# CF_Grove_Cape_v0_1.net
KiCad netlist of a schematic drawn in EAGLE
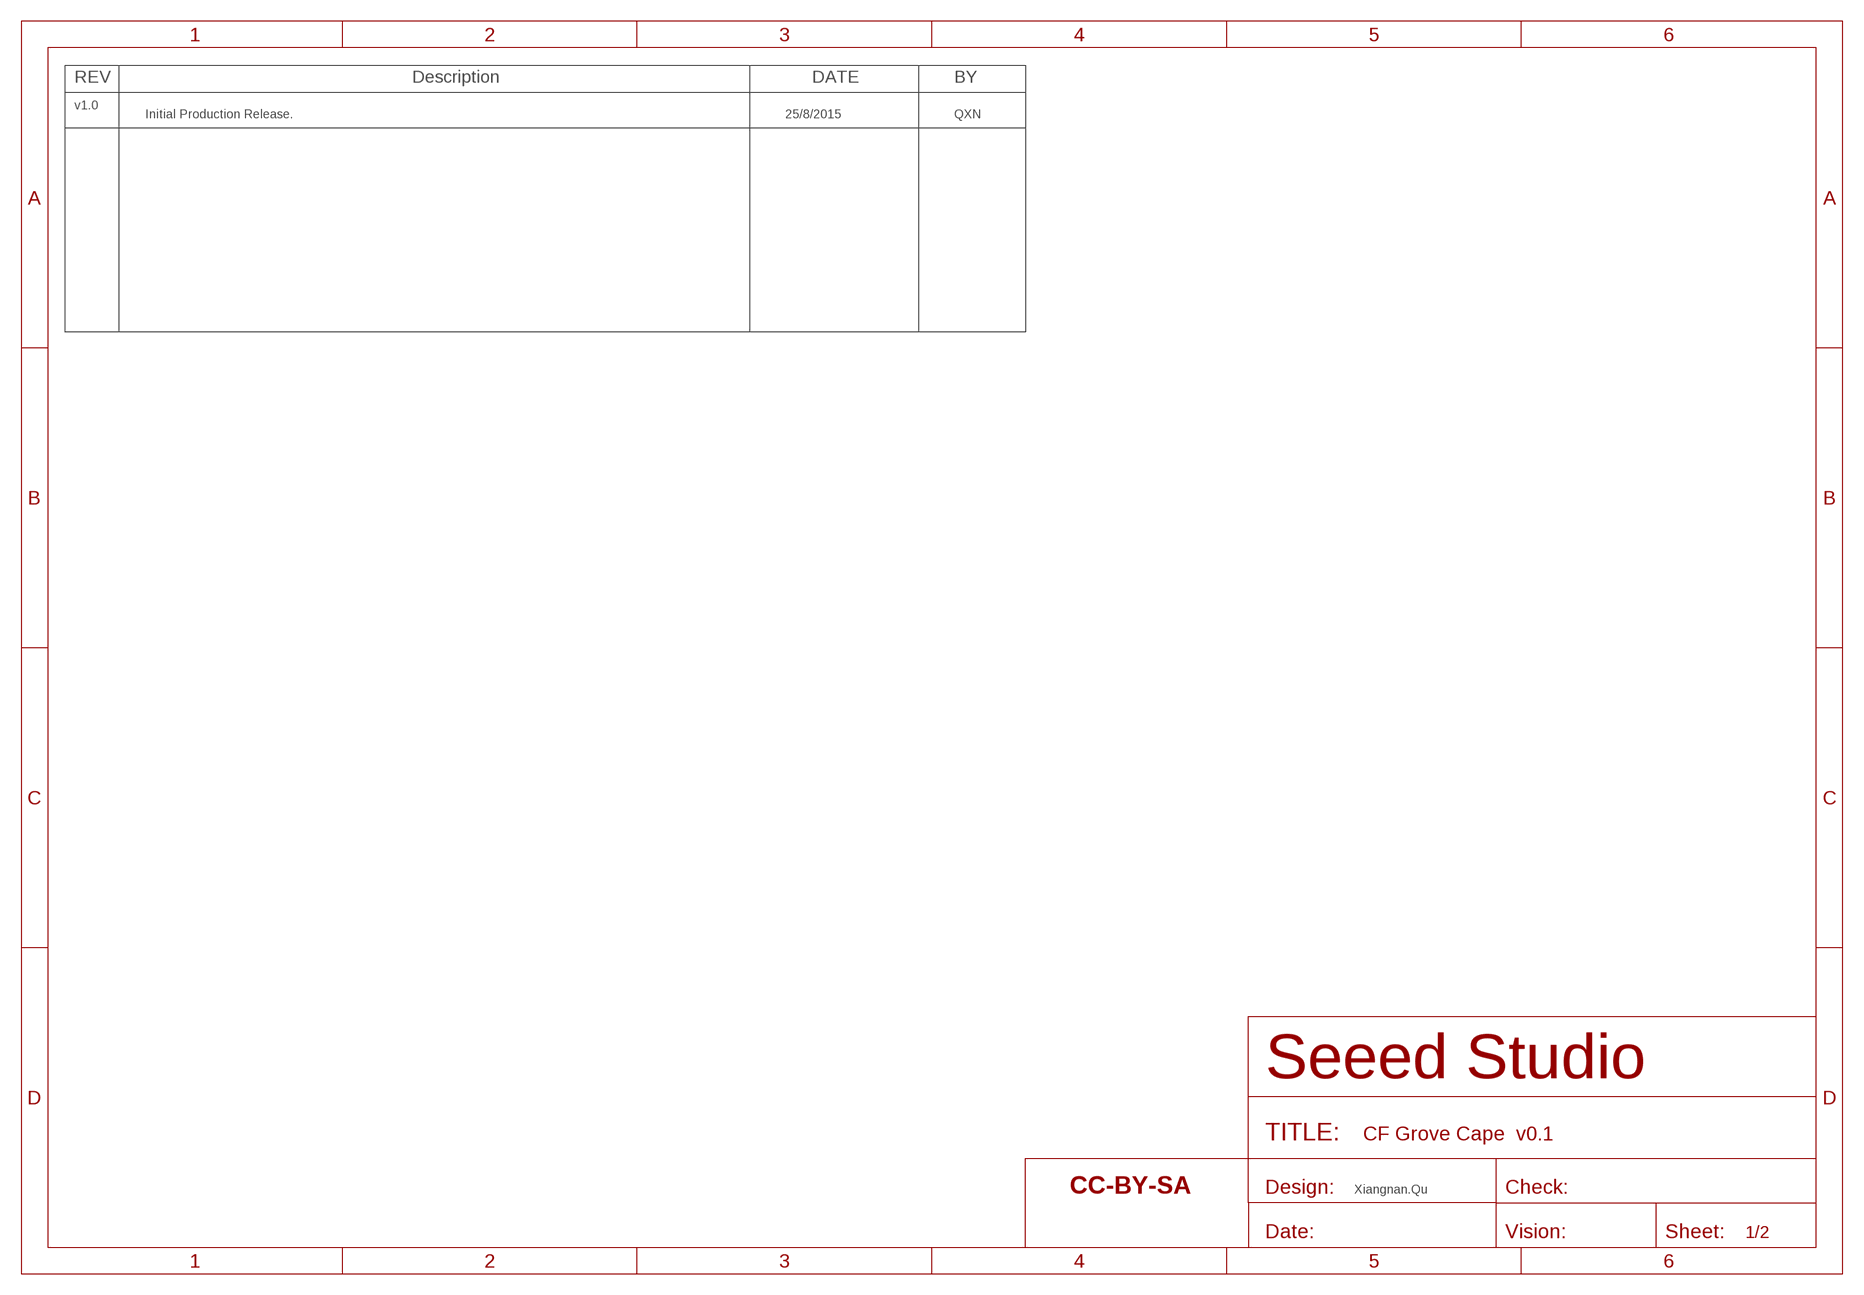
[diagram p0: schematic, sheet 1]
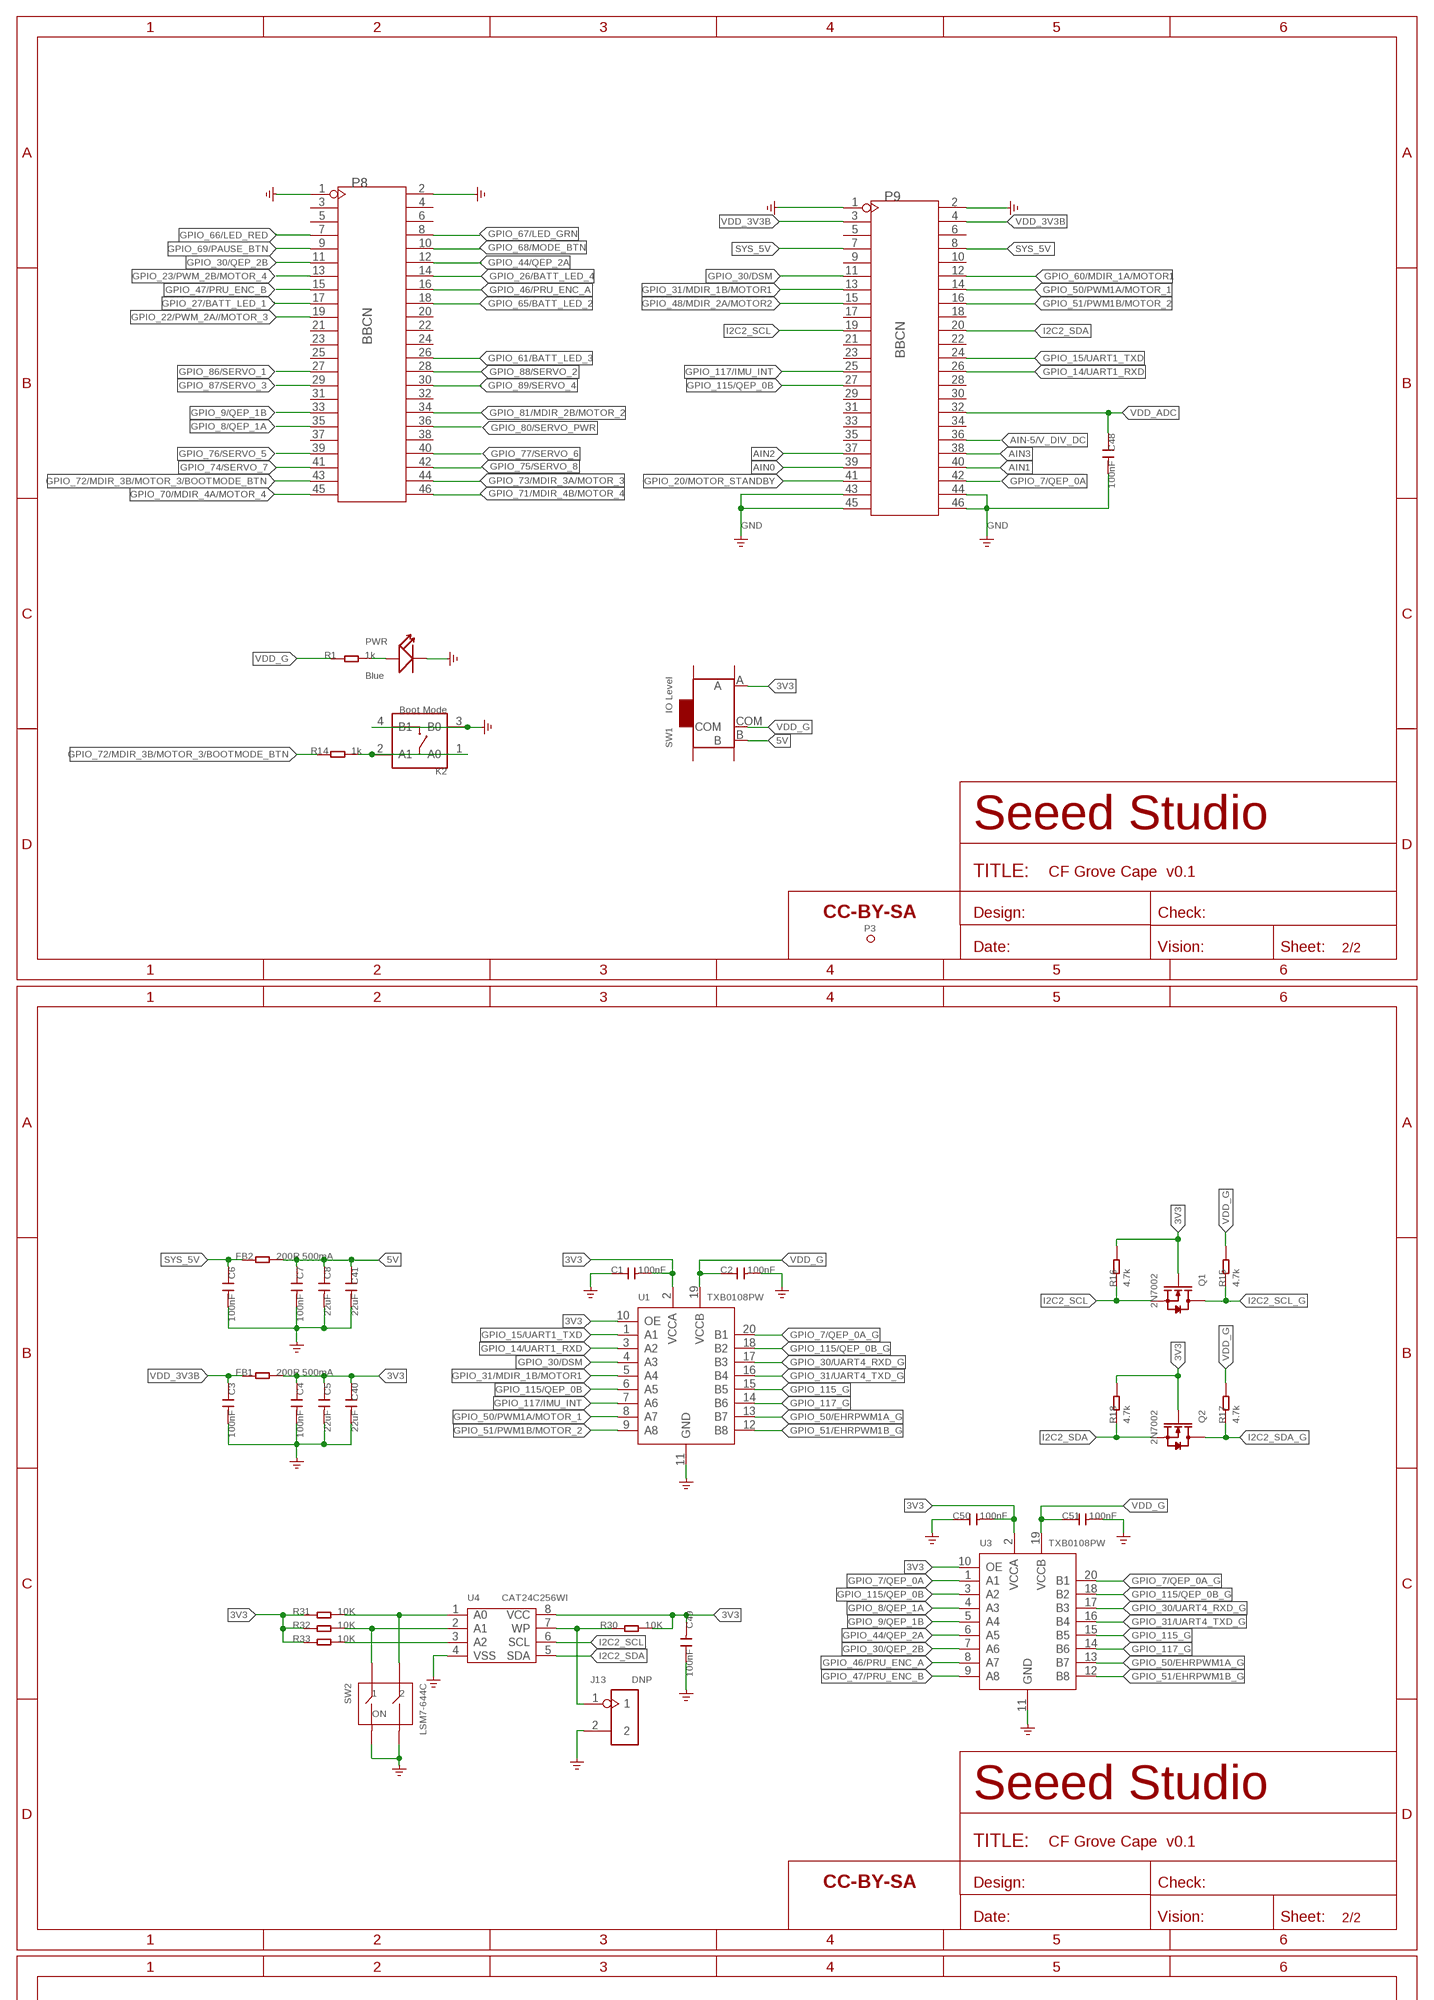
[diagram p1: schematic, sheet 2, part 1 of 2]
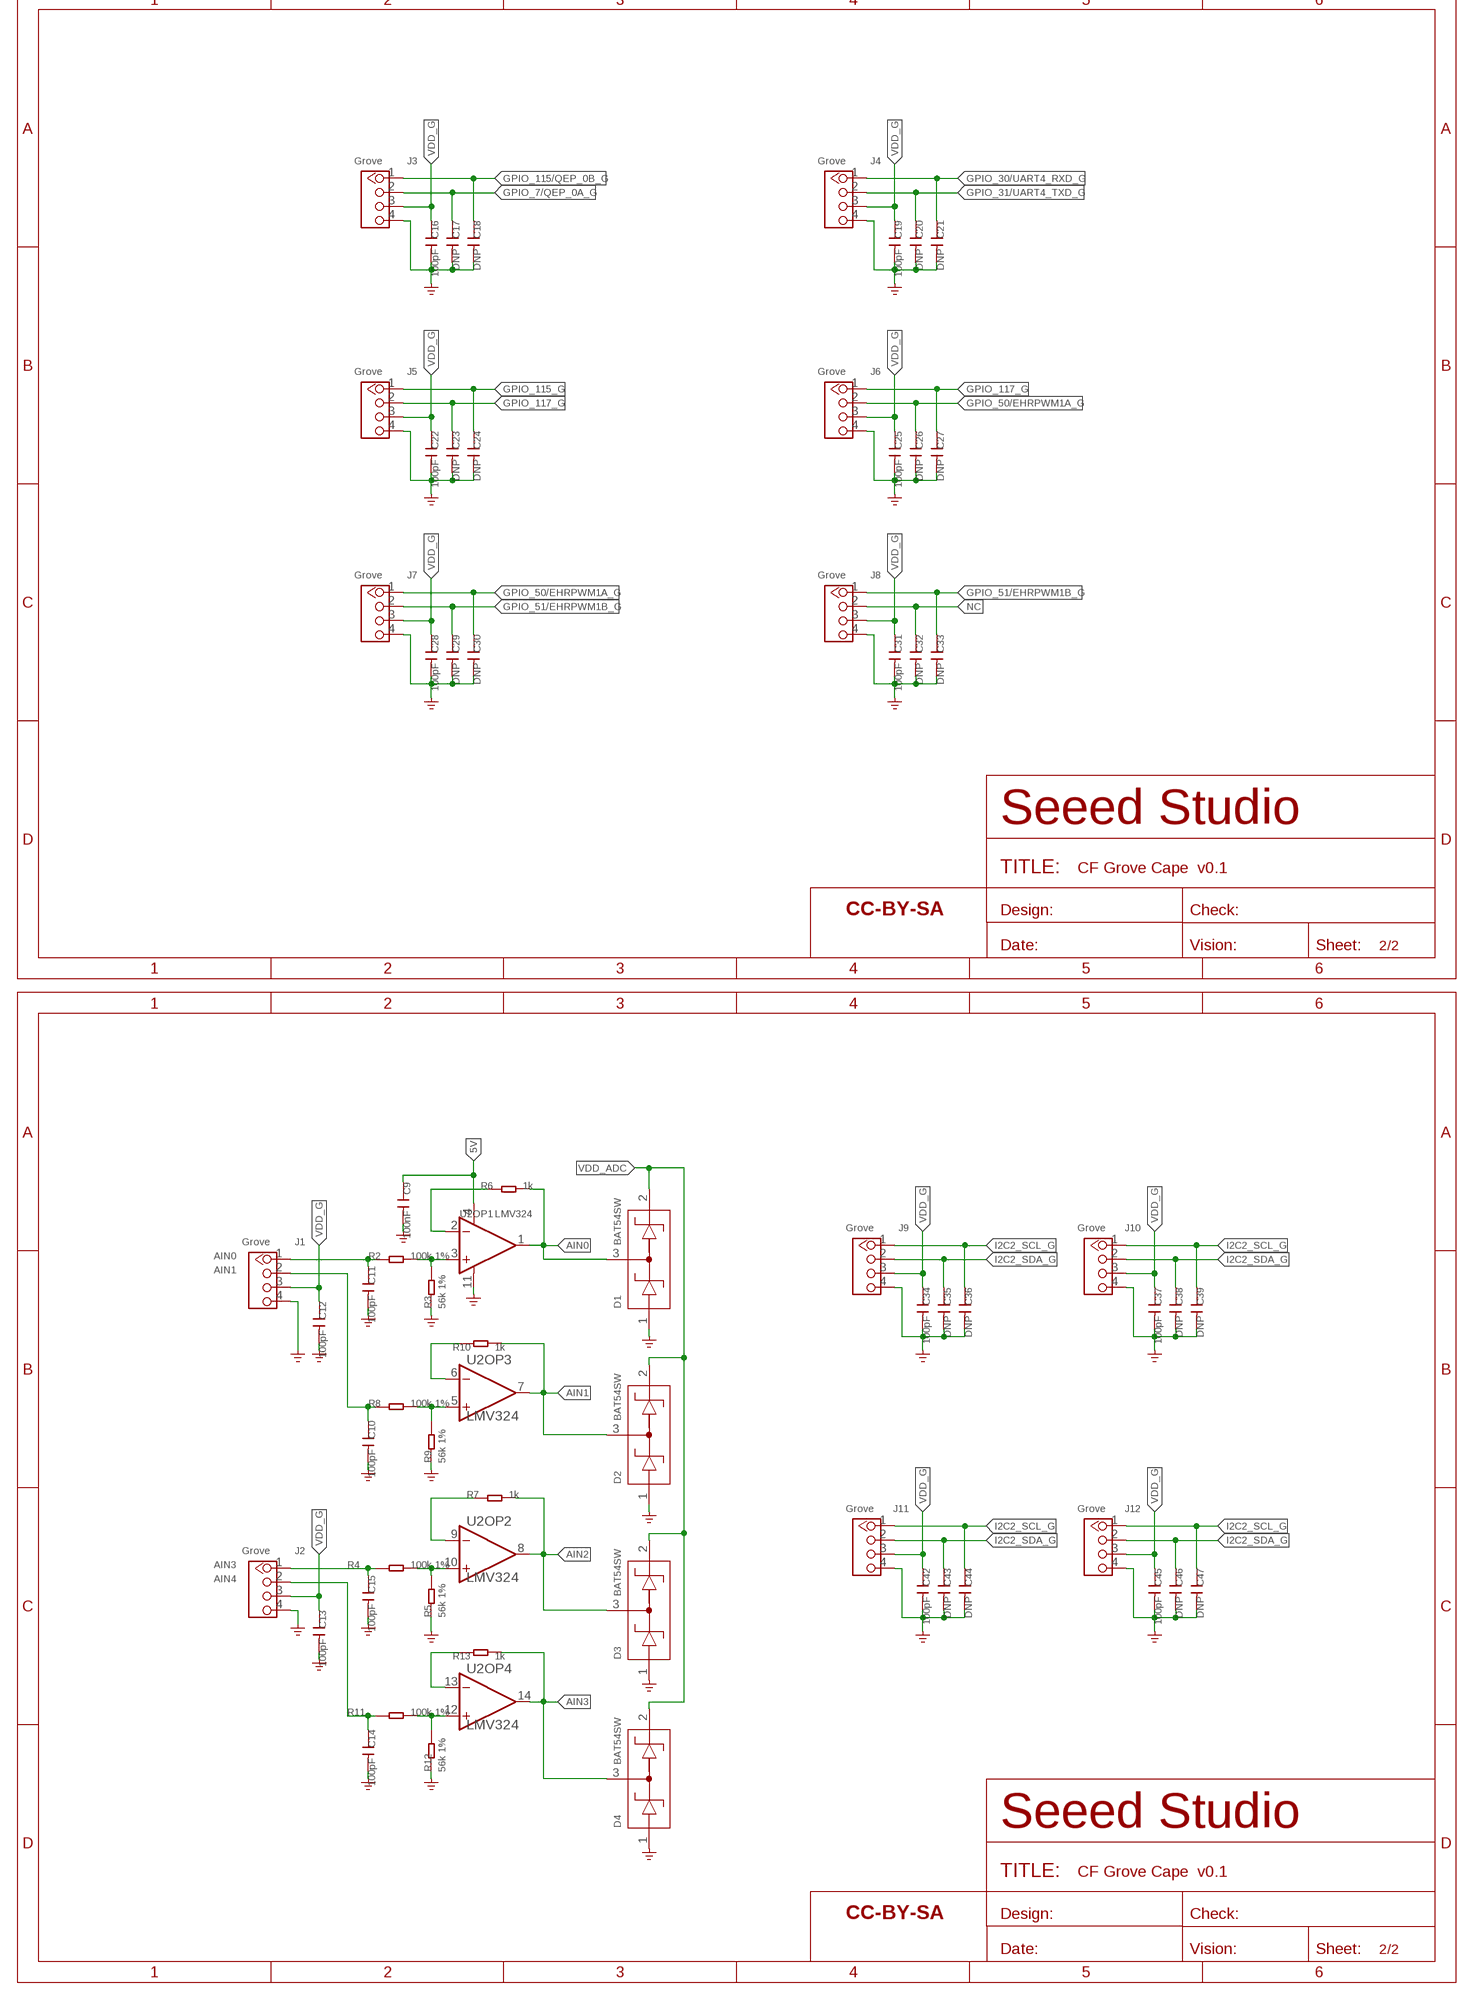
[diagram p2: schematic, sheet 2, part 2 of 2]

(export (version "E")
  (design (tool "Eeschema 10.0.6"))
  (components
    (comp (ref "FR1")
      (value "SEEEDSTUDIO-OPEN-SCH-FRAME")
      (footprint "eagle-import:SEEEDSTUDIO-PCB-FRAME")
      (libsource (lib "eagle-import") (part "SEEEDSTUDIO-OPEN-SCH-FRAME"))
    )
    (comp (ref "C1")
      (value "100nF")
      (footprint "eagle-import:C0402")
      (libsource (lib "eagle-import") (part "CAP-0402"))
    )
    (comp (ref "C2")
      (value "100nF")
      (footprint "eagle-import:C0402")
      (libsource (lib "eagle-import") (part "CAP-0402"))
    )
    (comp (ref "C3")
      (value "100nF")
      (footprint "eagle-import:C0402")
      (libsource (lib "eagle-import") (part "CAP-0402"))
    )
    (comp (ref "C4")
      (value "100nF")
      (footprint "eagle-import:C0402")
      (libsource (lib "eagle-import") (part "CAP-0402"))
    )
    (comp (ref "C5")
      (value "22uF")
      (footprint "eagle-import:C0805")
      (libsource (lib "eagle-import") (part "CAP-0805"))
    )
    (comp (ref "C6")
      (value "100nF")
      (footprint "eagle-import:C0402")
      (libsource (lib "eagle-import") (part "CAP-0402"))
    )
    (comp (ref "C7")
      (value "100nF")
      (footprint "eagle-import:C0402")
      (libsource (lib "eagle-import") (part "CAP-0402"))
    )
    (comp (ref "C8")
      (value "22uF")
      (footprint "eagle-import:C0805")
      (libsource (lib "eagle-import") (part "CAP-0805"))
    )
    (comp (ref "C9")
      (value "100nF")
      (footprint "eagle-import:C0402")
      (libsource (lib "eagle-import") (part "CAP-0402"))
    )
    (comp (ref "C10")
      (value "100pF")
      (footprint "eagle-import:C0402")
      (libsource (lib "eagle-import") (part "CAP-0402"))
    )
    (comp (ref "C11")
      (value "100pF")
      (footprint "eagle-import:C0402")
      (libsource (lib "eagle-import") (part "CAP-0402"))
    )
    (comp (ref "C12")
      (value "100pF")
      (footprint "eagle-import:C0402")
      (libsource (lib "eagle-import") (part "CAP-0402"))
    )
    (comp (ref "C13")
      (value "100pF")
      (footprint "eagle-import:C0402")
      (libsource (lib "eagle-import") (part "CAP-0402"))
    )
    (comp (ref "C14")
      (value "100pF")
      (footprint "eagle-import:C0402")
      (libsource (lib "eagle-import") (part "CAP-0402"))
    )
    (comp (ref "C15")
      (value "100pF")
      (footprint "eagle-import:C0402")
      (libsource (lib "eagle-import") (part "CAP-0402"))
    )
    (comp (ref "C16")
      (value "100pF")
      (footprint "eagle-import:C0402")
      (libsource (lib "eagle-import") (part "CAP-0402"))
    )
    (comp (ref "C17")
      (value "DNP")
      (footprint "eagle-import:C0402")
      (libsource (lib "eagle-import") (part "CAP-0402"))
    )
    (comp (ref "C18")
      (value "DNP")
      (footprint "eagle-import:C0402")
      (libsource (lib "eagle-import") (part "CAP-0402"))
    )
    (comp (ref "C19")
      (value "100pF")
      (footprint "eagle-import:C0402")
      (libsource (lib "eagle-import") (part "CAP-0402"))
    )
    (comp (ref "C20")
      (value "DNP")
      (footprint "eagle-import:C0402")
      (libsource (lib "eagle-import") (part "CAP-0402"))
    )
    (comp (ref "C21")
      (value "DNP")
      (footprint "eagle-import:C0402")
      (libsource (lib "eagle-import") (part "CAP-0402"))
    )
    (comp (ref "C22")
      (value "100pF")
      (footprint "eagle-import:C0402")
      (libsource (lib "eagle-import") (part "CAP-0402"))
    )
    (comp (ref "C23")
      (value "DNP")
      (footprint "eagle-import:C0402")
      (libsource (lib "eagle-import") (part "CAP-0402"))
    )
    (comp (ref "C24")
      (value "DNP")
      (footprint "eagle-import:C0402")
      (libsource (lib "eagle-import") (part "CAP-0402"))
    )
    (comp (ref "C25")
      (value "100pF")
      (footprint "eagle-import:C0402")
      (libsource (lib "eagle-import") (part "CAP-0402"))
    )
    (comp (ref "C26")
      (value "DNP")
      (footprint "eagle-import:C0402")
      (libsource (lib "eagle-import") (part "CAP-0402"))
    )
    (comp (ref "C27")
      (value "DNP")
      (footprint "eagle-import:C0402")
      (libsource (lib "eagle-import") (part "CAP-0402"))
    )
    (comp (ref "C28")
      (value "100pF")
      (footprint "eagle-import:C0402")
      (libsource (lib "eagle-import") (part "CAP-0402"))
    )
    (comp (ref "C29")
      (value "DNP")
      (footprint "eagle-import:C0402")
      (libsource (lib "eagle-import") (part "CAP-0402"))
    )
    (comp (ref "C30")
      (value "DNP")
      (footprint "eagle-import:C0402")
      (libsource (lib "eagle-import") (part "CAP-0402"))
    )
    (comp (ref "C31")
      (value "100pF")
      (footprint "eagle-import:C0402")
      (libsource (lib "eagle-import") (part "CAP-0402"))
    )
    (comp (ref "C32")
      (value "DNP")
      (footprint "eagle-import:C0402")
      (libsource (lib "eagle-import") (part "CAP-0402"))
    )
    (comp (ref "C33")
      (value "DNP")
      (footprint "eagle-import:C0402")
      (libsource (lib "eagle-import") (part "CAP-0402"))
    )
    (comp (ref "C34")
      (value "100pF")
      (footprint "eagle-import:C0402")
      (libsource (lib "eagle-import") (part "CAP-0402"))
    )
    (comp (ref "C35")
      (value "DNP")
      (footprint "eagle-import:C0402")
      (libsource (lib "eagle-import") (part "CAP-0402"))
    )
    (comp (ref "C36")
      (value "DNP")
      (footprint "eagle-import:C0402")
      (libsource (lib "eagle-import") (part "CAP-0402"))
    )
    (comp (ref "C37")
      (value "100pF")
      (footprint "eagle-import:C0402")
      (libsource (lib "eagle-import") (part "CAP-0402"))
    )
    (comp (ref "C38")
      (value "DNP")
      (footprint "eagle-import:C0402")
      (libsource (lib "eagle-import") (part "CAP-0402"))
    )
    (comp (ref "C39")
      (value "DNP")
      (footprint "eagle-import:C0402")
      (libsource (lib "eagle-import") (part "CAP-0402"))
    )
    (comp (ref "C40")
      (value "22uF")
      (footprint "eagle-import:C0805")
      (libsource (lib "eagle-import") (part "CAP-0805"))
    )
    (comp (ref "C41")
      (value "22uF")
      (footprint "eagle-import:C0805")
      (libsource (lib "eagle-import") (part "CAP-0805"))
    )
    (comp (ref "C42")
      (value "100pF")
      (footprint "eagle-import:C0402")
      (libsource (lib "eagle-import") (part "CAP-0402"))
    )
    (comp (ref "C43")
      (value "DNP")
      (footprint "eagle-import:C0402")
      (libsource (lib "eagle-import") (part "CAP-0402"))
    )
    (comp (ref "C44")
      (value "DNP")
      (footprint "eagle-import:C0402")
      (libsource (lib "eagle-import") (part "CAP-0402"))
    )
    (comp (ref "C45")
      (value "100pF")
      (footprint "eagle-import:C0402")
      (libsource (lib "eagle-import") (part "CAP-0402"))
    )
    (comp (ref "C46")
      (value "DNP")
      (footprint "eagle-import:C0402")
      (libsource (lib "eagle-import") (part "CAP-0402"))
    )
    (comp (ref "C47")
      (value "DNP")
      (footprint "eagle-import:C0402")
      (libsource (lib "eagle-import") (part "CAP-0402"))
    )
    (comp (ref "C48")
      (value "100nF")
      (footprint "eagle-import:C0402")
      (libsource (lib "eagle-import") (part "CAP-0402"))
    )
    (comp (ref "C49")
      (value "100nF")
      (footprint "eagle-import:C0402")
      (libsource (lib "eagle-import") (part "CAP-0402"))
    )
    (comp (ref "C50")
      (value "100nF")
      (footprint "eagle-import:C0402")
      (libsource (lib "eagle-import") (part "CAP-0402"))
    )
    (comp (ref "C51")
      (value "100nF")
      (footprint "eagle-import:C0402")
      (libsource (lib "eagle-import") (part "CAP-0402"))
    )
    (comp (ref "D1")
      (value "BAT54SW")
      (footprint "eagle-import:SOT-23")
      (libsource (lib "eagle-import") (part "D-SCHOTTKY-3P（BAT54SW)"))
    )
    (comp (ref "D2")
      (value "BAT54SW")
      (footprint "eagle-import:SOT-23")
      (libsource (lib "eagle-import") (part "D-SCHOTTKY-3P（BAT54SW)"))
    )
    (comp (ref "D3")
      (value "BAT54SW")
      (footprint "eagle-import:SOT-23")
      (libsource (lib "eagle-import") (part "D-SCHOTTKY-3P（BAT54SW)"))
    )
    (comp (ref "D4")
      (value "BAT54SW")
      (footprint "eagle-import:SOT-23")
      (libsource (lib "eagle-import") (part "D-SCHOTTKY-3P（BAT54SW)"))
    )
    (comp (ref "FB1")
      (value "200R 500mA")
      (footprint "eagle-import:R0603")
      (libsource (lib "eagle-import") (part "RES-0603"))
    )
    (comp (ref "FB2")
      (value "200R 500mA")
      (footprint "eagle-import:R0603")
      (libsource (lib "eagle-import") (part "RES-0603"))
    )
    (comp (ref "FR2")
      (value "SEEEDSTUDIO-OPEN-SCH-FRAME")
      (footprint "eagle-import:SEEEDSTUDIO-PCB-FRAME")
      (libsource (lib "eagle-import") (part "SEEEDSTUDIO-OPEN-SCH-FRAME"))
    )
    (comp (ref "FR3")
      (value "SEEEDSTUDIO-OPEN-SCH-FRAME")
      (footprint "eagle-import:SEEEDSTUDIO-PCB-FRAME")
      (libsource (lib "eagle-import") (part "SEEEDSTUDIO-OPEN-SCH-FRAME"))
    )
    (comp (ref "FR4")
      (value "SEEEDSTUDIO-OPEN-SCH-FRAME")
      (footprint "eagle-import:SEEEDSTUDIO-PCB-FRAME")
      (libsource (lib "eagle-import") (part "SEEEDSTUDIO-OPEN-SCH-FRAME"))
    )
    (comp (ref "FR5")
      (value "SEEEDSTUDIO-OPEN-SCH-FRAME")
      (footprint "eagle-import:SEEEDSTUDIO-PCB-FRAME")
      (libsource (lib "eagle-import") (part "SEEEDSTUDIO-OPEN-SCH-FRAME"))
    )
    (comp (ref "J1")
      (value "Grove")
      (footprint "eagle-import:HW4-2.0")
      (libsource (lib "eagle-import") (part "GROVE-CONNECTOR-DIP-2.0"))
    )
    (comp (ref "J2")
      (value "Grove")
      (footprint "eagle-import:HW4-2.0")
      (libsource (lib "eagle-import") (part "GROVE-CONNECTOR-DIP-2.0"))
    )
    (comp (ref "J3")
      (value "Grove")
      (footprint "eagle-import:HW4-2.0")
      (libsource (lib "eagle-import") (part "GROVE-CONNECTOR-DIP-2.0"))
    )
    (comp (ref "J4")
      (value "Grove")
      (footprint "eagle-import:HW4-2.0")
      (libsource (lib "eagle-import") (part "GROVE-CONNECTOR-DIP-2.0"))
    )
    (comp (ref "J5")
      (value "Grove")
      (footprint "eagle-import:HW4-2.0")
      (libsource (lib "eagle-import") (part "GROVE-CONNECTOR-DIP-2.0"))
    )
    (comp (ref "J6")
      (value "Grove")
      (footprint "eagle-import:HW4-2.0")
      (libsource (lib "eagle-import") (part "GROVE-CONNECTOR-DIP-2.0"))
    )
    (comp (ref "J7")
      (value "Grove")
      (footprint "eagle-import:HW4-2.0")
      (libsource (lib "eagle-import") (part "GROVE-CONNECTOR-DIP-2.0"))
    )
    (comp (ref "J8")
      (value "Grove")
      (footprint "eagle-import:HW4-2.0")
      (libsource (lib "eagle-import") (part "GROVE-CONNECTOR-DIP-2.0"))
    )
    (comp (ref "J9")
      (value "Grove")
      (footprint "eagle-import:HW4-2.0")
      (libsource (lib "eagle-import") (part "GROVE-CONNECTOR-DIP-2.0"))
    )
    (comp (ref "J10")
      (value "Grove")
      (footprint "eagle-import:HW4-2.0")
      (libsource (lib "eagle-import") (part "GROVE-CONNECTOR-DIP-2.0"))
    )
    (comp (ref "J11")
      (value "Grove")
      (footprint "eagle-import:HW4-2.0")
      (libsource (lib "eagle-import") (part "GROVE-CONNECTOR-DIP-2.0"))
    )
    (comp (ref "J12")
      (value "Grove")
      (footprint "eagle-import:HW4-2.0")
      (libsource (lib "eagle-import") (part "GROVE-CONNECTOR-DIP-2.0"))
    )
    (comp (ref "J13")
      (value "DNP")
      (footprint "eagle-import:H2-1.5")
      (libsource (lib "eagle-import") (part "HEADER-2P-1.5"))
    )
    (comp (ref "K2")
      (value "Boot Mode")
      (footprint "eagle-import:SW4P-SMD-4.5X3.2X2.5MM")
      (libsource (lib "eagle-import") (part "BUTTON-4P-4.5X3.2"))
    )
    (comp (ref "P3")
      (value "MARK-1.0'ANNULAR'")
      (footprint "eagle-import:ROUND-MARK-1.0")
      (fields (field (name "PARTNO") "DNP"))
      (libsource (lib "eagle-import") (part "MARK-1.0'ANNULAR'"))
    )
    (comp (ref "P8")
      (value "BBCN")
      (footprint "eagle-import:2X23P-2.54")
      (libsource (lib "eagle-import") (part "HEADER-2X23P"))
    )
    (comp (ref "P9")
      (value "BBCN")
      (footprint "eagle-import:2X23P-2.54")
      (libsource (lib "eagle-import") (part "HEADER-2X23P"))
    )
    (comp (ref "PWR")
      (value "Blue")
      (footprint "eagle-import:LED-0402")
      (libsource (lib "eagle-import") (part "LED-0402"))
    )
    (comp (ref "Q1")
      (value "2N7002")
      (footprint "eagle-import:SOT-23")
      (libsource (lib "eagle-import") (part "MOSFET-N'SOT23'"))
    )
    (comp (ref "Q2")
      (value "2N7002")
      (footprint "eagle-import:SOT-23")
      (libsource (lib "eagle-import") (part "MOSFET-N'SOT23'"))
    )
    (comp (ref "R1")
      (value "1k")
      (footprint "eagle-import:R0402")
      (libsource (lib "eagle-import") (part "RES-0402"))
    )
    (comp (ref "R2")
      (value "100k 1%")
      (footprint "eagle-import:R0402")
      (libsource (lib "eagle-import") (part "RES-0402"))
    )
    (comp (ref "R3")
      (value "56k 1%")
      (footprint "eagle-import:R0402")
      (libsource (lib "eagle-import") (part "RES-0402"))
    )
    (comp (ref "R4")
      (value "100k 1%")
      (footprint "eagle-import:R0402")
      (libsource (lib "eagle-import") (part "RES-0402"))
    )
    (comp (ref "R5")
      (value "56k 1%")
      (footprint "eagle-import:R0402")
      (libsource (lib "eagle-import") (part "RES-0402"))
    )
    (comp (ref "R6")
      (value "1k")
      (footprint "eagle-import:R0402")
      (libsource (lib "eagle-import") (part "RES-0402"))
    )
    (comp (ref "R7")
      (value "1k")
      (footprint "eagle-import:R0402")
      (libsource (lib "eagle-import") (part "RES-0402"))
    )
    (comp (ref "R8")
      (value "100k 1%")
      (footprint "eagle-import:R0402")
      (libsource (lib "eagle-import") (part "RES-0402"))
    )
    (comp (ref "R9")
      (value "56k 1%")
      (footprint "eagle-import:R0402")
      (libsource (lib "eagle-import") (part "RES-0402"))
    )
    (comp (ref "R10")
      (value "1k")
      (footprint "eagle-import:R0402")
      (libsource (lib "eagle-import") (part "RES-0402"))
    )
    (comp (ref "R11")
      (value "100k 1%")
      (footprint "eagle-import:R0402")
      (libsource (lib "eagle-import") (part "RES-0402"))
    )
    (comp (ref "R12")
      (value "56k 1%")
      (footprint "eagle-import:R0402")
      (libsource (lib "eagle-import") (part "RES-0402"))
    )
    (comp (ref "R13")
      (value "1k")
      (footprint "eagle-import:R0402")
      (libsource (lib "eagle-import") (part "RES-0402"))
    )
    (comp (ref "R14")
      (value "1k")
      (footprint "eagle-import:R0402")
      (libsource (lib "eagle-import") (part "RES-0402"))
    )
    (comp (ref "R15")
      (value "4.7k")
      (footprint "eagle-import:R0402")
      (libsource (lib "eagle-import") (part "RES-0402"))
    )
    (comp (ref "R16")
      (value "4.7k")
      (footprint "eagle-import:R0402")
      (libsource (lib "eagle-import") (part "RES-0402"))
    )
    (comp (ref "R17")
      (value "4.7k")
      (footprint "eagle-import:R0402")
      (libsource (lib "eagle-import") (part "RES-0402"))
    )
    (comp (ref "R18")
      (value "4.7k")
      (footprint "eagle-import:R0402")
      (libsource (lib "eagle-import") (part "RES-0402"))
    )
    (comp (ref "R30")
      (value "10K")
      (footprint "eagle-import:R0402")
      (libsource (lib "eagle-import") (part "RES-0402"))
    )
    (comp (ref "R31")
      (value "10K")
      (footprint "eagle-import:R0402")
      (libsource (lib "eagle-import") (part "RES-0402"))
    )
    (comp (ref "R32")
      (value "10K")
      (footprint "eagle-import:R0402")
      (libsource (lib "eagle-import") (part "RES-0402"))
    )
    (comp (ref "R33")
      (value "10K")
      (footprint "eagle-import:R0402")
      (libsource (lib "eagle-import") (part "RES-0402"))
    )
    (comp (ref "SW1")
      (value "IO Level")
      (footprint "eagle-import:SW7-SMD-L6.7X2.7X3.2MM")
      (libsource (lib "eagle-import") (part "SWITCH-3+4P"))
    )
    (comp (ref "SW2")
      (value "LSM7-644C")
      (footprint "eagle-import:SW4-SMD-5.08X6.8X3.3MM")
      (libsource (lib "eagle-import") (part "SWITCHES-4P'KM-02'"))
    )
    (comp (ref "U1")
      (value "TXB0108PW")
      (footprint "eagle-import:TSSOP20-0.65-6.5X4.4MM")
      (libsource (lib "eagle-import") (part "LOGIC-TXS0108EPWR"))
    )
    (comp (ref "U2")
      (value "LMV324")
      (footprint "eagle-import:TSSOP14-0.65-5X4.4MM")
      (libsource (lib "eagle-import") (part "AMPLIFIER-LMV324'PW'"))
    )
    (comp (ref "U3")
      (value "TXB0108PW")
      (footprint "eagle-import:TSSOP20-0.65-6.5X4.4MM")
      (libsource (lib "eagle-import") (part "LOGIC-TXS0108EPWR"))
    )
    (comp (ref "U4")
      (value "CAT24C256WI")
      (footprint "eagle-import:SOIC8-1.27-5X4MM")
      (libsource (lib "eagle-import") (part "MCU-EEPROM-CAT24C256"))
    )
  )
  (nets
    (net (code "1") (name "3V3") (class "Default")
      (node (ref "C1") (pin "2") (pinfunction "2_2") (pintype "passive"))
      (node (ref "C4") (pin "1") (pinfunction "1_1") (pintype "passive"))
      (node (ref "C40") (pin "1") (pinfunction "1_1") (pintype "passive"))
      (node (ref "C49") (pin "2") (pinfunction "2_2") (pintype "passive"))
      (node (ref "C5") (pin "1") (pinfunction "1_1") (pintype "passive"))
      (node (ref "C50") (pin "2") (pinfunction "2_2") (pintype "passive"))
      (node (ref "FB1") (pin "2") (pinfunction "2_2") (pintype "passive"))
      (node (ref "Q1") (pin "1") (pinfunction "G_1") (pintype "passive"))
      (node (ref "Q2") (pin "1") (pinfunction "G_1") (pintype "passive"))
      (node (ref "R16") (pin "2") (pinfunction "2_2") (pintype "passive"))
      (node (ref "R18") (pin "2") (pinfunction "2_2") (pintype "passive"))
      (node (ref "R30") (pin "1") (pinfunction "1_1") (pintype "passive"))
      (node (ref "R31") (pin "2") (pinfunction "2_2") (pintype "passive"))
      (node (ref "R32") (pin "2") (pinfunction "2_2") (pintype "passive"))
      (node (ref "R33") (pin "2") (pinfunction "2_2") (pintype "passive"))
      (node (ref "SW1") (pin "A") (pinfunction "A_A") (pintype "bidirectional"))
      (node (ref "U1") (pin "10") (pinfunction "OE_10") (pintype "bidirectional"))
      (node (ref "U1") (pin "2") (pinfunction "VCCA_2") (pintype "bidirectional"))
      (node (ref "U3") (pin "10") (pinfunction "OE_10") (pintype "bidirectional"))
      (node (ref "U3") (pin "2") (pinfunction "VCCA_2") (pintype "bidirectional"))
      (node (ref "U4") (pin "8") (pinfunction "VCC_8") (pintype "bidirectional"))
    )
    (net (code "2") (name "5V") (class "Default")
      (node (ref "C41") (pin "1") (pinfunction "1_1") (pintype "passive"))
      (node (ref "C7") (pin "1") (pinfunction "1_1") (pintype "passive"))
      (node (ref "C8") (pin "1") (pinfunction "1_1") (pintype "passive"))
      (node (ref "C9") (pin "1") (pinfunction "1_1") (pintype "passive"))
      (node (ref "FB2") (pin "2") (pinfunction "2_2") (pintype "passive"))
      (node (ref "SW1") (pin "B") (pinfunction "B_B") (pintype "bidirectional"))
      (node (ref "U2") (pin "4") (pinfunction "V+_4") (pintype "power_in"))
    )
    (net (code "3") (name "AIN-5{slash}V_DIV_DC") (class "Default")
      (node (ref "P9") (pin "36") (pinfunction "36_36") (pintype "bidirectional"))
    )
    (net (code "4") (name "AIN0") (class "Default")
      (node (ref "D1") (pin "3") (pinfunction "3_3") (pintype "bidirectional"))
      (node (ref "P9") (pin "39") (pinfunction "39_39") (pintype "bidirectional"))
      (node (ref "R6") (pin "2") (pinfunction "2_2") (pintype "passive"))
      (node (ref "U2") (pin "1") (pinfunction "OUT_1") (pintype "output"))
    )
    (net (code "5") (name "AIN1") (class "Default")
      (node (ref "D2") (pin "3") (pinfunction "3_3") (pintype "bidirectional"))
      (node (ref "P9") (pin "40") (pinfunction "40_40") (pintype "bidirectional"))
      (node (ref "R10") (pin "2") (pinfunction "2_2") (pintype "passive"))
      (node (ref "U2") (pin "7") (pinfunction "OUT_7") (pintype "output"))
    )
    (net (code "6") (name "AIN2") (class "Default")
      (node (ref "D3") (pin "3") (pinfunction "3_3") (pintype "bidirectional"))
      (node (ref "P9") (pin "37") (pinfunction "37_37") (pintype "bidirectional"))
      (node (ref "R7") (pin "2") (pinfunction "2_2") (pintype "passive"))
      (node (ref "U2") (pin "8") (pinfunction "OUT_8") (pintype "output"))
    )
    (net (code "7") (name "AIN3") (class "Default")
      (node (ref "D4") (pin "3") (pinfunction "3_3") (pintype "bidirectional"))
      (node (ref "P9") (pin "38") (pinfunction "38_38") (pintype "bidirectional"))
      (node (ref "R13") (pin "2") (pinfunction "2_2") (pintype "passive"))
      (node (ref "U2") (pin "14") (pinfunction "OUT_14") (pintype "output"))
    )
    (net (code "8") (name "GND") (class "Default")
      (node (ref "C1") (pin "1") (pinfunction "1_1") (pintype "passive"))
      (node (ref "C10") (pin "2") (pinfunction "2_2") (pintype "passive"))
      (node (ref "C11") (pin "2") (pinfunction "2_2") (pintype "passive"))
      (node (ref "C12") (pin "2") (pinfunction "2_2") (pintype "passive"))
      (node (ref "C13") (pin "2") (pinfunction "2_2") (pintype "passive"))
      (node (ref "C14") (pin "2") (pinfunction "2_2") (pintype "passive"))
      (node (ref "C15") (pin "2") (pinfunction "2_2") (pintype "passive"))
      (node (ref "C16") (pin "2") (pinfunction "2_2") (pintype "passive"))
      (node (ref "C17") (pin "2") (pinfunction "2_2") (pintype "passive"))
      (node (ref "C18") (pin "2") (pinfunction "2_2") (pintype "passive"))
      (node (ref "C19") (pin "2") (pinfunction "2_2") (pintype "passive"))
      (node (ref "C2") (pin "2") (pinfunction "2_2") (pintype "passive"))
      (node (ref "C20") (pin "2") (pinfunction "2_2") (pintype "passive"))
      (node (ref "C21") (pin "2") (pinfunction "2_2") (pintype "passive"))
      (node (ref "C22") (pin "2") (pinfunction "2_2") (pintype "passive"))
      (node (ref "C23") (pin "2") (pinfunction "2_2") (pintype "passive"))
      (node (ref "C24") (pin "2") (pinfunction "2_2") (pintype "passive"))
      (node (ref "C25") (pin "2") (pinfunction "2_2") (pintype "passive"))
      (node (ref "C26") (pin "2") (pinfunction "2_2") (pintype "passive"))
      (node (ref "C27") (pin "2") (pinfunction "2_2") (pintype "passive"))
      (node (ref "C28") (pin "2") (pinfunction "2_2") (pintype "passive"))
      (node (ref "C29") (pin "2") (pinfunction "2_2") (pintype "passive"))
      (node (ref "C3") (pin "2") (pinfunction "2_2") (pintype "passive"))
      (node (ref "C30") (pin "2") (pinfunction "2_2") (pintype "passive"))
      (node (ref "C31") (pin "2") (pinfunction "2_2") (pintype "passive"))
      (node (ref "C32") (pin "2") (pinfunction "2_2") (pintype "passive"))
      (node (ref "C33") (pin "2") (pinfunction "2_2") (pintype "passive"))
      (node (ref "C34") (pin "2") (pinfunction "2_2") (pintype "passive"))
      (node (ref "C35") (pin "2") (pinfunction "2_2") (pintype "passive"))
      (node (ref "C36") (pin "2") (pinfunction "2_2") (pintype "passive"))
      (node (ref "C37") (pin "2") (pinfunction "2_2") (pintype "passive"))
      (node (ref "C38") (pin "2") (pinfunction "2_2") (pintype "passive"))
      (node (ref "C39") (pin "2") (pinfunction "2_2") (pintype "passive"))
      (node (ref "C4") (pin "2") (pinfunction "2_2") (pintype "passive"))
      (node (ref "C40") (pin "2") (pinfunction "2_2") (pintype "passive"))
      (node (ref "C41") (pin "2") (pinfunction "2_2") (pintype "passive"))
      (node (ref "C42") (pin "2") (pinfunction "2_2") (pintype "passive"))
      (node (ref "C43") (pin "2") (pinfunction "2_2") (pintype "passive"))
      (node (ref "C44") (pin "2") (pinfunction "2_2") (pintype "passive"))
      (node (ref "C45") (pin "2") (pinfunction "2_2") (pintype "passive"))
      (node (ref "C46") (pin "2") (pinfunction "2_2") (pintype "passive"))
      (node (ref "C47") (pin "2") (pinfunction "2_2") (pintype "passive"))
      (node (ref "C48") (pin "2") (pinfunction "2_2") (pintype "passive"))
      (node (ref "C49") (pin "1") (pinfunction "1_1") (pintype "passive"))
      (node (ref "C5") (pin "2") (pinfunction "2_2") (pintype "passive"))
      (node (ref "C50") (pin "1") (pinfunction "1_1") (pintype "passive"))
      (node (ref "C51") (pin "2") (pinfunction "2_2") (pintype "passive"))
      (node (ref "C6") (pin "2") (pinfunction "2_2") (pintype "passive"))
      (node (ref "C7") (pin "2") (pinfunction "2_2") (pintype "passive"))
      (node (ref "C8") (pin "2") (pinfunction "2_2") (pintype "passive"))
      (node (ref "C9") (pin "2") (pinfunction "2_2") (pintype "passive"))
      (node (ref "D1") (pin "1") (pinfunction "1_1") (pintype "bidirectional"))
      (node (ref "D2") (pin "1") (pinfunction "1_1") (pintype "bidirectional"))
      (node (ref "D3") (pin "1") (pinfunction "1_1") (pintype "bidirectional"))
      (node (ref "D4") (pin "1") (pinfunction "1_1") (pintype "bidirectional"))
      (node (ref "J1") (pin "4") (pinfunction "4_4") (pintype "bidirectional"))
      (node (ref "J10") (pin "4") (pinfunction "4_4") (pintype "bidirectional"))
      (node (ref "J11") (pin "4") (pinfunction "4_4") (pintype "bidirectional"))
      (node (ref "J12") (pin "4") (pinfunction "4_4") (pintype "bidirectional"))
      (node (ref "J13") (pin "2") (pinfunction "2_2") (pintype "bidirectional"))
      (node (ref "J2") (pin "4") (pinfunction "4_4") (pintype "bidirectional"))
      (node (ref "J3") (pin "4") (pinfunction "4_4") (pintype "bidirectional"))
      (node (ref "J4") (pin "4") (pinfunction "4_4") (pintype "bidirectional"))
      (node (ref "J5") (pin "4") (pinfunction "4_4") (pintype "bidirectional"))
      (node (ref "J6") (pin "4") (pinfunction "4_4") (pintype "bidirectional"))
      (node (ref "J7") (pin "4") (pinfunction "4_4") (pintype "bidirectional"))
      (node (ref "J8") (pin "4") (pinfunction "4_4") (pintype "bidirectional"))
      (node (ref "J9") (pin "4") (pinfunction "4_4") (pintype "bidirectional"))
      (node (ref "K2") (pin "3") (pinfunction "B0_3") (pintype "bidirectional"))
      (node (ref "K2") (pin "4") (pinfunction "B1_4") (pintype "bidirectional"))
      (node (ref "P8") (pin "1") (pinfunction "1_1") (pintype "bidirectional"))
      (node (ref "P8") (pin "2") (pinfunction "2_2") (pintype "bidirectional"))
      (node (ref "P9") (pin "1") (pinfunction "1_1") (pintype "bidirectional"))
      (node (ref "P9") (pin "2") (pinfunction "2_2") (pintype "bidirectional"))
      (node (ref "P9") (pin "43") (pinfunction "43_43") (pintype "bidirectional"))
      (node (ref "P9") (pin "44") (pinfunction "44_44") (pintype "bidirectional"))
      (node (ref "P9") (pin "45") (pinfunction "45_45") (pintype "bidirectional"))
      (node (ref "P9") (pin "46") (pinfunction "46_46") (pintype "bidirectional"))
      (node (ref "PWR") (pin "-") (pinfunction "-_-") (pintype "passive"))
      (node (ref "R12") (pin "1") (pinfunction "1_1") (pintype "passive"))
      (node (ref "R3") (pin "1") (pinfunction "1_1") (pintype "passive"))
      (node (ref "R5") (pin "1") (pinfunction "1_1") (pintype "passive"))
      (node (ref "R9") (pin "1") (pinfunction "1_1") (pintype "passive"))
      (node (ref "SW2") (pin "3") (pinfunction "3_3") (pintype "bidirectional"))
      (node (ref "SW2") (pin "4") (pinfunction "4_4") (pintype "bidirectional"))
      (node (ref "U1") (pin "11") (pinfunction "GND_11") (pintype "bidirectional"))
      (node (ref "U2") (pin "11") (pinfunction "V-_11") (pintype "power_in"))
      (node (ref "U3") (pin "11") (pinfunction "GND_11") (pintype "bidirectional"))
      (node (ref "U4") (pin "4") (pinfunction "VSS_4") (pintype "bidirectional"))
    )
    (net (code "9") (name "GPIO_7{slash}QEP_0A") (class "Default")
      (node (ref "P9") (pin "42") (pinfunction "42_42") (pintype "bidirectional"))
      (node (ref "U3") (pin "1") (pinfunction "A1_1") (pintype "bidirectional"))
    )
    (net (code "10") (name "GPIO_7{slash}QEP_0A_G") (class "Default")
      (node (ref "C17") (pin "1") (pinfunction "1_1") (pintype "passive"))
      (node (ref "J3") (pin "2") (pinfunction "2_2") (pintype "bidirectional"))
      (node (ref "U1") (pin "20") (pinfunction "B1_20") (pintype "bidirectional"))
      (node (ref "U3") (pin "20") (pinfunction "B1_20") (pintype "bidirectional"))
    )
    (net (code "11") (name "GPIO_8{slash}QEP_1A") (class "Default")
      (node (ref "P8") (pin "35") (pinfunction "35_35") (pintype "bidirectional"))
      (node (ref "U3") (pin "4") (pinfunction "A3_4") (pintype "bidirectional"))
    )
    (net (code "12") (name "GPIO_9{slash}QEP_1B") (class "Default")
      (node (ref "P8") (pin "33") (pinfunction "33_33") (pintype "bidirectional"))
      (node (ref "U3") (pin "5") (pinfunction "A4_5") (pintype "bidirectional"))
    )
    (net (code "13") (name "GPIO_14{slash}UART1_RXD") (class "Default")
      (node (ref "P9") (pin "26") (pinfunction "26_26") (pintype "bidirectional"))
      (node (ref "U1") (pin "3") (pinfunction "A2_3") (pintype "bidirectional"))
    )
    (net (code "14") (name "GPIO_15{slash}UART1_TXD") (class "Default")
      (node (ref "P9") (pin "24") (pinfunction "24_24") (pintype "bidirectional"))
      (node (ref "U1") (pin "1") (pinfunction "A1_1") (pintype "bidirectional"))
    )
    (net (code "15") (name "GPIO_20{slash}MOTOR_STANDBY") (class "Default")
      (node (ref "P9") (pin "41") (pinfunction "41_41") (pintype "bidirectional"))
    )
    (net (code "16") (name "GPIO_22{slash}PWM_2A{slash}{slash}MOTOR_3") (class "Default")
      (node (ref "P8") (pin "19") (pinfunction "19_19") (pintype "bidirectional"))
    )
    (net (code "17") (name "GPIO_23{slash}PWM_2B{slash}MOTOR_4") (class "Default")
      (node (ref "P8") (pin "13") (pinfunction "13_13") (pintype "bidirectional"))
    )
    (net (code "18") (name "GPIO_26{slash}BATT_LED_4") (class "Default")
      (node (ref "P8") (pin "14") (pinfunction "14_14") (pintype "bidirectional"))
    )
    (net (code "19") (name "GPIO_27{slash}BATT_LED_1") (class "Default")
      (node (ref "P8") (pin "17") (pinfunction "17_17") (pintype "bidirectional"))
    )
    (net (code "20") (name "GPIO_30{slash}DSM") (class "Default")
      (node (ref "P9") (pin "11") (pinfunction "11_11") (pintype "bidirectional"))
      (node (ref "U1") (pin "4") (pinfunction "A3_4") (pintype "bidirectional"))
    )
    (net (code "21") (name "GPIO_30{slash}QEP_2B") (class "Default")
      (node (ref "P8") (pin "11") (pinfunction "11_11") (pintype "bidirectional"))
      (node (ref "U3") (pin "7") (pinfunction "A6_7") (pintype "bidirectional"))
    )
    (net (code "22") (name "GPIO_30{slash}UART4_RXD_G") (class "Default")
      (node (ref "C21") (pin "1") (pinfunction "1_1") (pintype "passive"))
      (node (ref "J4") (pin "1") (pinfunction "1_1") (pintype "bidirectional"))
      (node (ref "U1") (pin "17") (pinfunction "B3_17") (pintype "bidirectional"))
      (node (ref "U3") (pin "17") (pinfunction "B3_17") (pintype "bidirectional"))
    )
    (net (code "23") (name "GPIO_31{slash}MDIR_1B{slash}MOTOR1") (class "Default")
      (node (ref "P9") (pin "13") (pinfunction "13_13") (pintype "bidirectional"))
      (node (ref "U1") (pin "5") (pinfunction "A4_5") (pintype "bidirectional"))
    )
    (net (code "24") (name "GPIO_31{slash}UART4_TXD_G") (class "Default")
      (node (ref "C20") (pin "1") (pinfunction "1_1") (pintype "passive"))
      (node (ref "J4") (pin "2") (pinfunction "2_2") (pintype "bidirectional"))
      (node (ref "U1") (pin "16") (pinfunction "B4_16") (pintype "bidirectional"))
      (node (ref "U3") (pin "16") (pinfunction "B4_16") (pintype "bidirectional"))
    )
    (net (code "25") (name "GPIO_44{slash}QEP_2A") (class "Default")
      (node (ref "P8") (pin "12") (pinfunction "12_12") (pintype "bidirectional"))
      (node (ref "U3") (pin "6") (pinfunction "A5_6") (pintype "bidirectional"))
    )
    (net (code "26") (name "GPIO_46{slash}PRU_ENC_A") (class "Default")
      (node (ref "P8") (pin "16") (pinfunction "16_16") (pintype "bidirectional"))
      (node (ref "U3") (pin "8") (pinfunction "A7_8") (pintype "bidirectional"))
    )
    (net (code "27") (name "GPIO_47{slash}PRU_ENC_B") (class "Default")
      (node (ref "P8") (pin "15") (pinfunction "15_15") (pintype "bidirectional"))
      (node (ref "U3") (pin "9") (pinfunction "A8_9") (pintype "bidirectional"))
    )
    (net (code "28") (name "GPIO_48{slash}MDIR_2A{slash}MOTOR2") (class "Default")
      (node (ref "P9") (pin "15") (pinfunction "15_15") (pintype "bidirectional"))
    )
    (net (code "29") (name "GPIO_50{slash}EHRPWM1A_G") (class "Default")
      (node (ref "C26") (pin "1") (pinfunction "1_1") (pintype "passive"))
      (node (ref "C30") (pin "1") (pinfunction "1_1") (pintype "passive"))
      (node (ref "J6") (pin "2") (pinfunction "2_2") (pintype "bidirectional"))
      (node (ref "J7") (pin "1") (pinfunction "1_1") (pintype "bidirectional"))
      (node (ref "U1") (pin "13") (pinfunction "B7_13") (pintype "bidirectional"))
      (node (ref "U3") (pin "13") (pinfunction "B7_13") (pintype "bidirectional"))
    )
    (net (code "30") (name "GPIO_50{slash}PWM1A{slash}MOTOR_1") (class "Default")
      (node (ref "P9") (pin "14") (pinfunction "14_14") (pintype "bidirectional"))
      (node (ref "U1") (pin "8") (pinfunction "A7_8") (pintype "bidirectional"))
    )
    (net (code "31") (name "GPIO_51{slash}EHRPWM1B_G") (class "Default")
      (node (ref "C29") (pin "1") (pinfunction "1_1") (pintype "passive"))
      (node (ref "C33") (pin "1") (pinfunction "1_1") (pintype "passive"))
      (node (ref "J7") (pin "2") (pinfunction "2_2") (pintype "bidirectional"))
      (node (ref "J8") (pin "1") (pinfunction "1_1") (pintype "bidirectional"))
      (node (ref "U1") (pin "12") (pinfunction "B8_12") (pintype "bidirectional"))
      (node (ref "U3") (pin "12") (pinfunction "B8_12") (pintype "bidirectional"))
    )
    (net (code "32") (name "GPIO_51{slash}PWM1B{slash}MOTOR_2") (class "Default")
      (node (ref "P9") (pin "16") (pinfunction "16_16") (pintype "bidirectional"))
      (node (ref "U1") (pin "9") (pinfunction "A8_9") (pintype "bidirectional"))
    )
    (net (code "33") (name "GPIO_60{slash}MDIR_1A{slash}MOTOR1") (class "Default")
      (node (ref "P9") (pin "12") (pinfunction "12_12") (pintype "bidirectional"))
    )
    (net (code "34") (name "GPIO_61{slash}BATT_LED_3") (class "Default")
      (node (ref "P8") (pin "26") (pinfunction "26_26") (pintype "bidirectional"))
    )
    (net (code "35") (name "GPIO_65{slash}BATT_LED_2") (class "Default")
      (node (ref "P8") (pin "18") (pinfunction "18_18") (pintype "bidirectional"))
    )
    (net (code "36") (name "GPIO_66{slash}LED_RED") (class "Default")
      (node (ref "P8") (pin "7") (pinfunction "7_7") (pintype "bidirectional"))
    )
    (net (code "37") (name "GPIO_67{slash}LED_GRN") (class "Default")
      (node (ref "P8") (pin "8") (pinfunction "8_8") (pintype "bidirectional"))
    )
    (net (code "38") (name "GPIO_68{slash}MODE_BTN") (class "Default")
      (node (ref "P8") (pin "10") (pinfunction "10_10") (pintype "bidirectional"))
    )
    (net (code "39") (name "GPIO_69{slash}PAUSE_BTN") (class "Default")
      (node (ref "P8") (pin "9") (pinfunction "9_9") (pintype "bidirectional"))
    )
    (net (code "40") (name "GPIO_70{slash}MDIR_4A{slash}MOTOR_4") (class "Default")
      (node (ref "P8") (pin "45") (pinfunction "45_45") (pintype "bidirectional"))
    )
    (net (code "41") (name "GPIO_71{slash}MDIR_4B{slash}MOTOR_4") (class "Default")
      (node (ref "P8") (pin "46") (pinfunction "46_46") (pintype "bidirectional"))
    )
    (net (code "42") (name "GPIO_72{slash}MDIR_3B{slash}MOTOR_3{slash}BOOTMODE_BTN") (class "Default")
      (node (ref "P8") (pin "43") (pinfunction "43_43") (pintype "bidirectional"))
      (node (ref "R14") (pin "1") (pinfunction "1_1") (pintype "passive"))
    )
    (net (code "43") (name "GPIO_73{slash}MDIR_3A{slash}MOTOR_3") (class "Default")
      (node (ref "P8") (pin "44") (pinfunction "44_44") (pintype "bidirectional"))
    )
    (net (code "44") (name "GPIO_74{slash}SERVO_7") (class "Default")
      (node (ref "P8") (pin "41") (pinfunction "41_41") (pintype "bidirectional"))
    )
    (net (code "45") (name "GPIO_75{slash}SERVO_8") (class "Default")
      (node (ref "P8") (pin "42") (pinfunction "42_42") (pintype "bidirectional"))
    )
    (net (code "46") (name "GPIO_76{slash}SERVO_5") (class "Default")
      (node (ref "P8") (pin "39") (pinfunction "39_39") (pintype "bidirectional"))
    )
    (net (code "47") (name "GPIO_77{slash}SERVO_6") (class "Default")
      (node (ref "P8") (pin "40") (pinfunction "40_40") (pintype "bidirectional"))
    )
    (net (code "48") (name "GPIO_80{slash}SERVO_PWR") (class "Default")
      (node (ref "P8") (pin "36") (pinfunction "36_36") (pintype "bidirectional"))
    )
    (net (code "49") (name "GPIO_81{slash}MDIR_2B{slash}MOTOR_2") (class "Default")
      (node (ref "P8") (pin "34") (pinfunction "34_34") (pintype "bidirectional"))
    )
    (net (code "50") (name "GPIO_86{slash}SERVO_1") (class "Default")
      (node (ref "P8") (pin "27") (pinfunction "27_27") (pintype "bidirectional"))
    )
    (net (code "51") (name "GPIO_87{slash}SERVO_3") (class "Default")
      (node (ref "P8") (pin "29") (pinfunction "29_29") (pintype "bidirectional"))
    )
    (net (code "52") (name "GPIO_88{slash}SERVO_2") (class "Default")
      (node (ref "P8") (pin "28") (pinfunction "28_28") (pintype "bidirectional"))
    )
    (net (code "53") (name "GPIO_89{slash}SERVO_4") (class "Default")
      (node (ref "P8") (pin "30") (pinfunction "30_30") (pintype "bidirectional"))
    )
    (net (code "54") (name "GPIO_115_G") (class "Default")
      (node (ref "C24") (pin "1") (pinfunction "1_1") (pintype "passive"))
      (node (ref "J5") (pin "1") (pinfunction "1_1") (pintype "bidirectional"))
      (node (ref "U1") (pin "15") (pinfunction "B5_15") (pintype "bidirectional"))
      (node (ref "U3") (pin "15") (pinfunction "B5_15") (pintype "bidirectional"))
    )
    (net (code "55") (name "GPIO_115{slash}QEP_0B") (class "Default")
      (node (ref "P9") (pin "27") (pinfunction "27_27") (pintype "bidirectional"))
      (node (ref "U1") (pin "6") (pinfunction "A5_6") (pintype "bidirectional"))
      (node (ref "U3") (pin "3") (pinfunction "A2_3") (pintype "bidirectional"))
    )
    (net (code "56") (name "GPIO_115{slash}QEP_0B_G") (class "Default")
      (node (ref "C18") (pin "1") (pinfunction "1_1") (pintype "passive"))
      (node (ref "J3") (pin "1") (pinfunction "1_1") (pintype "bidirectional"))
      (node (ref "U1") (pin "18") (pinfunction "B2_18") (pintype "bidirectional"))
      (node (ref "U3") (pin "18") (pinfunction "B2_18") (pintype "bidirectional"))
    )
    (net (code "57") (name "GPIO_117_G") (class "Default")
      (node (ref "C23") (pin "1") (pinfunction "1_1") (pintype "passive"))
      (node (ref "C27") (pin "1") (pinfunction "1_1") (pintype "passive"))
      (node (ref "J5") (pin "2") (pinfunction "2_2") (pintype "bidirectional"))
      (node (ref "J6") (pin "1") (pinfunction "1_1") (pintype "bidirectional"))
      (node (ref "U1") (pin "14") (pinfunction "B6_14") (pintype "bidirectional"))
      (node (ref "U3") (pin "14") (pinfunction "B6_14") (pintype "bidirectional"))
    )
    (net (code "58") (name "GPIO_117{slash}IMU_INT") (class "Default")
      (node (ref "P9") (pin "25") (pinfunction "25_25") (pintype "bidirectional"))
      (node (ref "U1") (pin "7") (pinfunction "A6_7") (pintype "bidirectional"))
    )
    (net (code "59") (name "I2C2_SCL") (class "Default")
      (node (ref "P9") (pin "19") (pinfunction "19_19") (pintype "bidirectional"))
      (node (ref "Q1") (pin "2") (pinfunction "S_2") (pintype "passive"))
      (node (ref "R16") (pin "1") (pinfunction "1_1") (pintype "passive"))
      (node (ref "U4") (pin "6") (pinfunction "SCL_6") (pintype "bidirectional"))
    )
    (net (code "60") (name "I2C2_SCL_G") (class "Default")
      (node (ref "C36") (pin "1") (pinfunction "1_1") (pintype "passive"))
      (node (ref "C39") (pin "1") (pinfunction "1_1") (pintype "passive"))
      (node (ref "C44") (pin "1") (pinfunction "1_1") (pintype "passive"))
      (node (ref "C47") (pin "1") (pinfunction "1_1") (pintype "passive"))
      (node (ref "J10") (pin "1") (pinfunction "1_1") (pintype "bidirectional"))
      (node (ref "J11") (pin "1") (pinfunction "1_1") (pintype "bidirectional"))
      (node (ref "J12") (pin "1") (pinfunction "1_1") (pintype "bidirectional"))
      (node (ref "J9") (pin "1") (pinfunction "1_1") (pintype "bidirectional"))
      (node (ref "Q1") (pin "3") (pinfunction "D_3") (pintype "passive"))
      (node (ref "R15") (pin "1") (pinfunction "1_1") (pintype "passive"))
    )
    (net (code "61") (name "I2C2_SDA") (class "Default")
      (node (ref "P9") (pin "20") (pinfunction "20_20") (pintype "bidirectional"))
      (node (ref "Q2") (pin "2") (pinfunction "S_2") (pintype "passive"))
      (node (ref "R18") (pin "1") (pinfunction "1_1") (pintype "passive"))
      (node (ref "U4") (pin "5") (pinfunction "SDA_5") (pintype "bidirectional"))
    )
    (net (code "62") (name "I2C2_SDA_G") (class "Default")
      (node (ref "C35") (pin "1") (pinfunction "1_1") (pintype "passive"))
      (node (ref "C38") (pin "1") (pinfunction "1_1") (pintype "passive"))
      (node (ref "C43") (pin "1") (pinfunction "1_1") (pintype "passive"))
      (node (ref "C46") (pin "1") (pinfunction "1_1") (pintype "passive"))
      (node (ref "J10") (pin "2") (pinfunction "2_2") (pintype "bidirectional"))
      (node (ref "J11") (pin "2") (pinfunction "2_2") (pintype "bidirectional"))
      (node (ref "J12") (pin "2") (pinfunction "2_2") (pintype "bidirectional"))
      (node (ref "J9") (pin "2") (pinfunction "2_2") (pintype "bidirectional"))
      (node (ref "Q2") (pin "3") (pinfunction "D_3") (pintype "passive"))
      (node (ref "R17") (pin "1") (pinfunction "1_1") (pintype "passive"))
    )
    (net (code "63") (name "NC") (class "Default")
      (node (ref "C32") (pin "1") (pinfunction "1_1") (pintype "passive"))
      (node (ref "J8") (pin "2") (pinfunction "2_2") (pintype "bidirectional"))
    )
    (net (code "64") (name "Net-(C10-Pad1)") (class "Default")
      (node (ref "C10") (pin "1") (pinfunction "1_1") (pintype "passive"))
      (node (ref "J1") (pin "2") (pinfunction "2_2") (pintype "bidirectional"))
      (node (ref "R8") (pin "1") (pinfunction "1_1") (pintype "passive"))
    )
    (net (code "65") (name "Net-(C11-Pad1)") (class "Default")
      (node (ref "C11") (pin "1") (pinfunction "1_1") (pintype "passive"))
      (node (ref "J1") (pin "1") (pinfunction "1_1") (pintype "bidirectional"))
      (node (ref "R2") (pin "1") (pinfunction "1_1") (pintype "passive"))
    )
    (net (code "66") (name "Net-(C14-Pad1)") (class "Default")
      (node (ref "C14") (pin "1") (pinfunction "1_1") (pintype "passive"))
      (node (ref "J2") (pin "2") (pinfunction "2_2") (pintype "bidirectional"))
      (node (ref "R11") (pin "1") (pinfunction "1_1") (pintype "passive"))
    )
    (net (code "67") (name "Net-(C15-Pad1)") (class "Default")
      (node (ref "C15") (pin "1") (pinfunction "1_1") (pintype "passive"))
      (node (ref "J2") (pin "1") (pinfunction "1_1") (pintype "bidirectional"))
      (node (ref "R4") (pin "1") (pinfunction "1_1") (pintype "passive"))
    )
    (net (code "68") (name "Net-(K2-A0)") (class "Default")
      (node (ref "K2") (pin "1") (pinfunction "A0_1") (pintype "bidirectional"))
      (node (ref "K2") (pin "2") (pinfunction "A1_2") (pintype "bidirectional"))
      (node (ref "R14") (pin "2") (pinfunction "2_2") (pintype "passive"))
    )
    (net (code "69") (name "Net-(PWR-Pad+)") (class "Default")
      (node (ref "PWR") (pin "+") (pinfunction "+_+") (pintype "passive"))
      (node (ref "R1") (pin "2") (pinfunction "2_2") (pintype "passive"))
    )
    (net (code "70") (name "Net-(U2A-IN+)") (class "Default")
      (node (ref "R2") (pin "2") (pinfunction "2_2") (pintype "passive"))
      (node (ref "R3") (pin "2") (pinfunction "2_2") (pintype "passive"))
      (node (ref "U2") (pin "3") (pinfunction "IN+_3") (pintype "input"))
    )
    (net (code "71") (name "Net-(U2A-IN-)") (class "Default")
      (node (ref "R6") (pin "1") (pinfunction "1_1") (pintype "passive"))
      (node (ref "U2") (pin "2") (pinfunction "IN-_2") (pintype "input"))
    )
    (net (code "72") (name "Net-(U2B-IN+)") (class "Default")
      (node (ref "R4") (pin "2") (pinfunction "2_2") (pintype "passive"))
      (node (ref "R5") (pin "2") (pinfunction "2_2") (pintype "passive"))
      (node (ref "U2") (pin "10") (pinfunction "IN+_10") (pintype "input"))
    )
    (net (code "73") (name "Net-(U2B-IN-)") (class "Default")
      (node (ref "R7") (pin "1") (pinfunction "1_1") (pintype "passive"))
      (node (ref "U2") (pin "9") (pinfunction "IN-_9") (pintype "input"))
    )
    (net (code "74") (name "Net-(U2C-IN+)") (class "Default")
      (node (ref "R8") (pin "2") (pinfunction "2_2") (pintype "passive"))
      (node (ref "R9") (pin "2") (pinfunction "2_2") (pintype "passive"))
      (node (ref "U2") (pin "5") (pinfunction "IN+_5") (pintype "input"))
    )
    (net (code "75") (name "Net-(U2C-IN-)") (class "Default")
      (node (ref "R10") (pin "1") (pinfunction "1_1") (pintype "passive"))
      (node (ref "U2") (pin "6") (pinfunction "IN-_6") (pintype "input"))
    )
    (net (code "76") (name "Net-(U2D-IN+)") (class "Default")
      (node (ref "R11") (pin "2") (pinfunction "2_2") (pintype "passive"))
      (node (ref "R12") (pin "2") (pinfunction "2_2") (pintype "passive"))
      (node (ref "U2") (pin "12") (pinfunction "IN+_12") (pintype "input"))
    )
    (net (code "77") (name "Net-(U2D-IN-)") (class "Default")
      (node (ref "R13") (pin "1") (pinfunction "1_1") (pintype "passive"))
      (node (ref "U2") (pin "13") (pinfunction "IN-_13") (pintype "input"))
    )
    (net (code "78") (name "Net-(U4-A0)") (class "Default")
      (node (ref "R31") (pin "1") (pinfunction "1_1") (pintype "passive"))
      (node (ref "SW2") (pin "2") (pinfunction "2_2") (pintype "bidirectional"))
      (node (ref "U4") (pin "1") (pinfunction "A0_1") (pintype "bidirectional"))
    )
    (net (code "79") (name "Net-(U4-A1)") (class "Default")
      (node (ref "R32") (pin "1") (pinfunction "1_1") (pintype "passive"))
      (node (ref "SW2") (pin "1") (pinfunction "1_1") (pintype "bidirectional"))
      (node (ref "U4") (pin "2") (pinfunction "A1_2") (pintype "bidirectional"))
    )
    (net (code "80") (name "Net-(U4-A2)") (class "Default")
      (node (ref "R33") (pin "1") (pinfunction "1_1") (pintype "passive"))
      (node (ref "U4") (pin "3") (pinfunction "A2_3") (pintype "bidirectional"))
    )
    (net (code "81") (name "Net-(U4-WP)") (class "Default")
      (node (ref "J13") (pin "1") (pinfunction "1_1") (pintype "bidirectional"))
      (node (ref "R30") (pin "2") (pinfunction "2_2") (pintype "passive"))
      (node (ref "U4") (pin "7") (pinfunction "WP_7") (pintype "bidirectional"))
    )
    (net (code "82") (name "SYS_5V") (class "Default")
      (node (ref "C6") (pin "1") (pinfunction "1_1") (pintype "passive"))
      (node (ref "FB2") (pin "1") (pinfunction "1_1") (pintype "passive"))
      (node (ref "P9") (pin "7") (pinfunction "7_7") (pintype "bidirectional"))
      (node (ref "P9") (pin "8") (pinfunction "8_8") (pintype "bidirectional"))
    )
    (net (code "83") (name "VDD_3V3B") (class "Default")
      (node (ref "C3") (pin "1") (pinfunction "1_1") (pintype "passive"))
      (node (ref "FB1") (pin "1") (pinfunction "1_1") (pintype "passive"))
      (node (ref "P9") (pin "3") (pinfunction "3_3") (pintype "bidirectional"))
      (node (ref "P9") (pin "4") (pinfunction "4_4") (pintype "bidirectional"))
    )
    (net (code "84") (name "VDD_ADC") (class "Default")
      (node (ref "C48") (pin "1") (pinfunction "1_1") (pintype "passive"))
      (node (ref "D1") (pin "2") (pinfunction "2_2") (pintype "bidirectional"))
      (node (ref "D2") (pin "2") (pinfunction "2_2") (pintype "bidirectional"))
      (node (ref "D3") (pin "2") (pinfunction "2_2") (pintype "bidirectional"))
      (node (ref "D4") (pin "2") (pinfunction "2_2") (pintype "bidirectional"))
      (node (ref "P9") (pin "32") (pinfunction "32_32") (pintype "bidirectional"))
    )
    (net (code "85") (name "VDD_G") (class "Default")
      (node (ref "C12") (pin "1") (pinfunction "1_1") (pintype "passive"))
      (node (ref "C13") (pin "1") (pinfunction "1_1") (pintype "passive"))
      (node (ref "C16") (pin "1") (pinfunction "1_1") (pintype "passive"))
      (node (ref "C19") (pin "1") (pinfunction "1_1") (pintype "passive"))
      (node (ref "C2") (pin "1") (pinfunction "1_1") (pintype "passive"))
      (node (ref "C22") (pin "1") (pinfunction "1_1") (pintype "passive"))
      (node (ref "C25") (pin "1") (pinfunction "1_1") (pintype "passive"))
      (node (ref "C28") (pin "1") (pinfunction "1_1") (pintype "passive"))
      (node (ref "C31") (pin "1") (pinfunction "1_1") (pintype "passive"))
      (node (ref "C34") (pin "1") (pinfunction "1_1") (pintype "passive"))
      (node (ref "C37") (pin "1") (pinfunction "1_1") (pintype "passive"))
      (node (ref "C42") (pin "1") (pinfunction "1_1") (pintype "passive"))
      (node (ref "C45") (pin "1") (pinfunction "1_1") (pintype "passive"))
      (node (ref "C51") (pin "1") (pinfunction "1_1") (pintype "passive"))
      (node (ref "J1") (pin "3") (pinfunction "3_3") (pintype "bidirectional"))
      (node (ref "J10") (pin "3") (pinfunction "3_3") (pintype "bidirectional"))
      (node (ref "J11") (pin "3") (pinfunction "3_3") (pintype "bidirectional"))
      (node (ref "J12") (pin "3") (pinfunction "3_3") (pintype "bidirectional"))
      (node (ref "J2") (pin "3") (pinfunction "3_3") (pintype "bidirectional"))
      (node (ref "J3") (pin "3") (pinfunction "3_3") (pintype "bidirectional"))
      (node (ref "J4") (pin "3") (pinfunction "3_3") (pintype "bidirectional"))
      (node (ref "J5") (pin "3") (pinfunction "3_3") (pintype "bidirectional"))
      (node (ref "J6") (pin "3") (pinfunction "3_3") (pintype "bidirectional"))
      (node (ref "J7") (pin "3") (pinfunction "3_3") (pintype "bidirectional"))
      (node (ref "J8") (pin "3") (pinfunction "3_3") (pintype "bidirectional"))
      (node (ref "J9") (pin "3") (pinfunction "3_3") (pintype "bidirectional"))
      (node (ref "R1") (pin "1") (pinfunction "1_1") (pintype "passive"))
      (node (ref "R15") (pin "2") (pinfunction "2_2") (pintype "passive"))
      (node (ref "R17") (pin "2") (pinfunction "2_2") (pintype "passive"))
      (node (ref "SW1") (pin "COM") (pinfunction "COM_COM") (pintype "bidirectional"))
      (node (ref "U1") (pin "19") (pinfunction "VCCB_19") (pintype "bidirectional"))
      (node (ref "U3") (pin "19") (pinfunction "VCCB_19") (pintype "bidirectional"))
    )
    (net (code "86") (name "unconnected-(P8-Pad3)") (class "Default")
      (node (ref "P8") (pin "3") (pinfunction "3_3") (pintype "bidirectional"))
    )
    (net (code "87") (name "unconnected-(P8-Pad4)") (class "Default")
      (node (ref "P8") (pin "4") (pinfunction "4_4") (pintype "bidirectional"))
    )
    (net (code "88") (name "unconnected-(P8-Pad5)") (class "Default")
      (node (ref "P8") (pin "5") (pinfunction "5_5") (pintype "bidirectional"))
    )
    (net (code "89") (name "unconnected-(P8-Pad6)") (class "Default")
      (node (ref "P8") (pin "6") (pinfunction "6_6") (pintype "bidirectional"))
    )
    (net (code "90") (name "unconnected-(P8-Pad20)") (class "Default")
      (node (ref "P8") (pin "20") (pinfunction "20_20") (pintype "bidirectional"))
    )
    (net (code "91") (name "unconnected-(P8-Pad21)") (class "Default")
      (node (ref "P8") (pin "21") (pinfunction "21_21") (pintype "bidirectional"))
    )
    (net (code "92") (name "unconnected-(P8-Pad22)") (class "Default")
      (node (ref "P8") (pin "22") (pinfunction "22_22") (pintype "bidirectional"))
    )
    (net (code "93") (name "unconnected-(P8-Pad23)") (class "Default")
      (node (ref "P8") (pin "23") (pinfunction "23_23") (pintype "bidirectional"))
    )
    (net (code "94") (name "unconnected-(P8-Pad24)") (class "Default")
      (node (ref "P8") (pin "24") (pinfunction "24_24") (pintype "bidirectional"))
    )
    (net (code "95") (name "unconnected-(P8-Pad25)") (class "Default")
      (node (ref "P8") (pin "25") (pinfunction "25_25") (pintype "bidirectional"))
    )
    (net (code "96") (name "unconnected-(P8-Pad31)") (class "Default")
      (node (ref "P8") (pin "31") (pinfunction "31_31") (pintype "bidirectional"))
    )
    (net (code "97") (name "unconnected-(P8-Pad32)") (class "Default")
      (node (ref "P8") (pin "32") (pinfunction "32_32") (pintype "bidirectional"))
    )
    (net (code "98") (name "unconnected-(P8-Pad37)") (class "Default")
      (node (ref "P8") (pin "37") (pinfunction "37_37") (pintype "bidirectional"))
    )
    (net (code "99") (name "unconnected-(P8-Pad38)") (class "Default")
      (node (ref "P8") (pin "38") (pinfunction "38_38") (pintype "bidirectional"))
    )
    (net (code "100") (name "unconnected-(P9-Pad5)") (class "Default")
      (node (ref "P9") (pin "5") (pinfunction "5_5") (pintype "bidirectional"))
    )
    (net (code "101") (name "unconnected-(P9-Pad6)") (class "Default")
      (node (ref "P9") (pin "6") (pinfunction "6_6") (pintype "bidirectional"))
    )
    (net (code "102") (name "unconnected-(P9-Pad9)") (class "Default")
      (node (ref "P9") (pin "9") (pinfunction "9_9") (pintype "bidirectional"))
    )
    (net (code "103") (name "unconnected-(P9-Pad10)") (class "Default")
      (node (ref "P9") (pin "10") (pinfunction "10_10") (pintype "bidirectional"))
    )
    (net (code "104") (name "unconnected-(P9-Pad17)") (class "Default")
      (node (ref "P9") (pin "17") (pinfunction "17_17") (pintype "bidirectional"))
    )
    (net (code "105") (name "unconnected-(P9-Pad18)") (class "Default")
      (node (ref "P9") (pin "18") (pinfunction "18_18") (pintype "bidirectional"))
    )
    (net (code "106") (name "unconnected-(P9-Pad21)") (class "Default")
      (node (ref "P9") (pin "21") (pinfunction "21_21") (pintype "bidirectional"))
    )
    (net (code "107") (name "unconnected-(P9-Pad22)") (class "Default")
      (node (ref "P9") (pin "22") (pinfunction "22_22") (pintype "bidirectional"))
    )
    (net (code "108") (name "unconnected-(P9-Pad23)") (class "Default")
      (node (ref "P9") (pin "23") (pinfunction "23_23") (pintype "bidirectional"))
    )
    (net (code "109") (name "unconnected-(P9-Pad28)") (class "Default")
      (node (ref "P9") (pin "28") (pinfunction "28_28") (pintype "bidirectional"))
    )
    (net (code "110") (name "unconnected-(P9-Pad29)") (class "Default")
      (node (ref "P9") (pin "29") (pinfunction "29_29") (pintype "bidirectional"))
    )
    (net (code "111") (name "unconnected-(P9-Pad30)") (class "Default")
      (node (ref "P9") (pin "30") (pinfunction "30_30") (pintype "bidirectional"))
    )
    (net (code "112") (name "unconnected-(P9-Pad31)") (class "Default")
      (node (ref "P9") (pin "31") (pinfunction "31_31") (pintype "bidirectional"))
    )
    (net (code "113") (name "unconnected-(P9-Pad33)") (class "Default")
      (node (ref "P9") (pin "33") (pinfunction "33_33") (pintype "bidirectional"))
    )
    (net (code "114") (name "unconnected-(P9-Pad34)") (class "Default")
      (node (ref "P9") (pin "34") (pinfunction "34_34") (pintype "bidirectional"))
    )
    (net (code "115") (name "unconnected-(P9-Pad35)") (class "Default")
      (node (ref "P9") (pin "35") (pinfunction "35_35") (pintype "bidirectional"))
    )
    (net (code "116") (name "unconnected-(SW1-PadSS1)") (class "Default")
      (node (ref "SW1") (pin "SS1") (pinfunction "SS1_SS1") (pintype "bidirectional"))
    )
    (net (code "117") (name "unconnected-(SW1-PadSS2)") (class "Default")
      (node (ref "SW1") (pin "SS2") (pinfunction "SS2_SS2") (pintype "bidirectional"))
    )
    (net (code "118") (name "unconnected-(SW1-PadSS3)") (class "Default")
      (node (ref "SW1") (pin "SS3") (pinfunction "SS3_SS3") (pintype "bidirectional"))
    )
    (net (code "119") (name "unconnected-(SW1-PadSS4)") (class "Default")
      (node (ref "SW1") (pin "SS4") (pinfunction "SS4_SS4") (pintype "bidirectional"))
    )
  )
)
